# Relays_Multiplexer.net
KiCad netlist of a schematic drawn in EAGLE
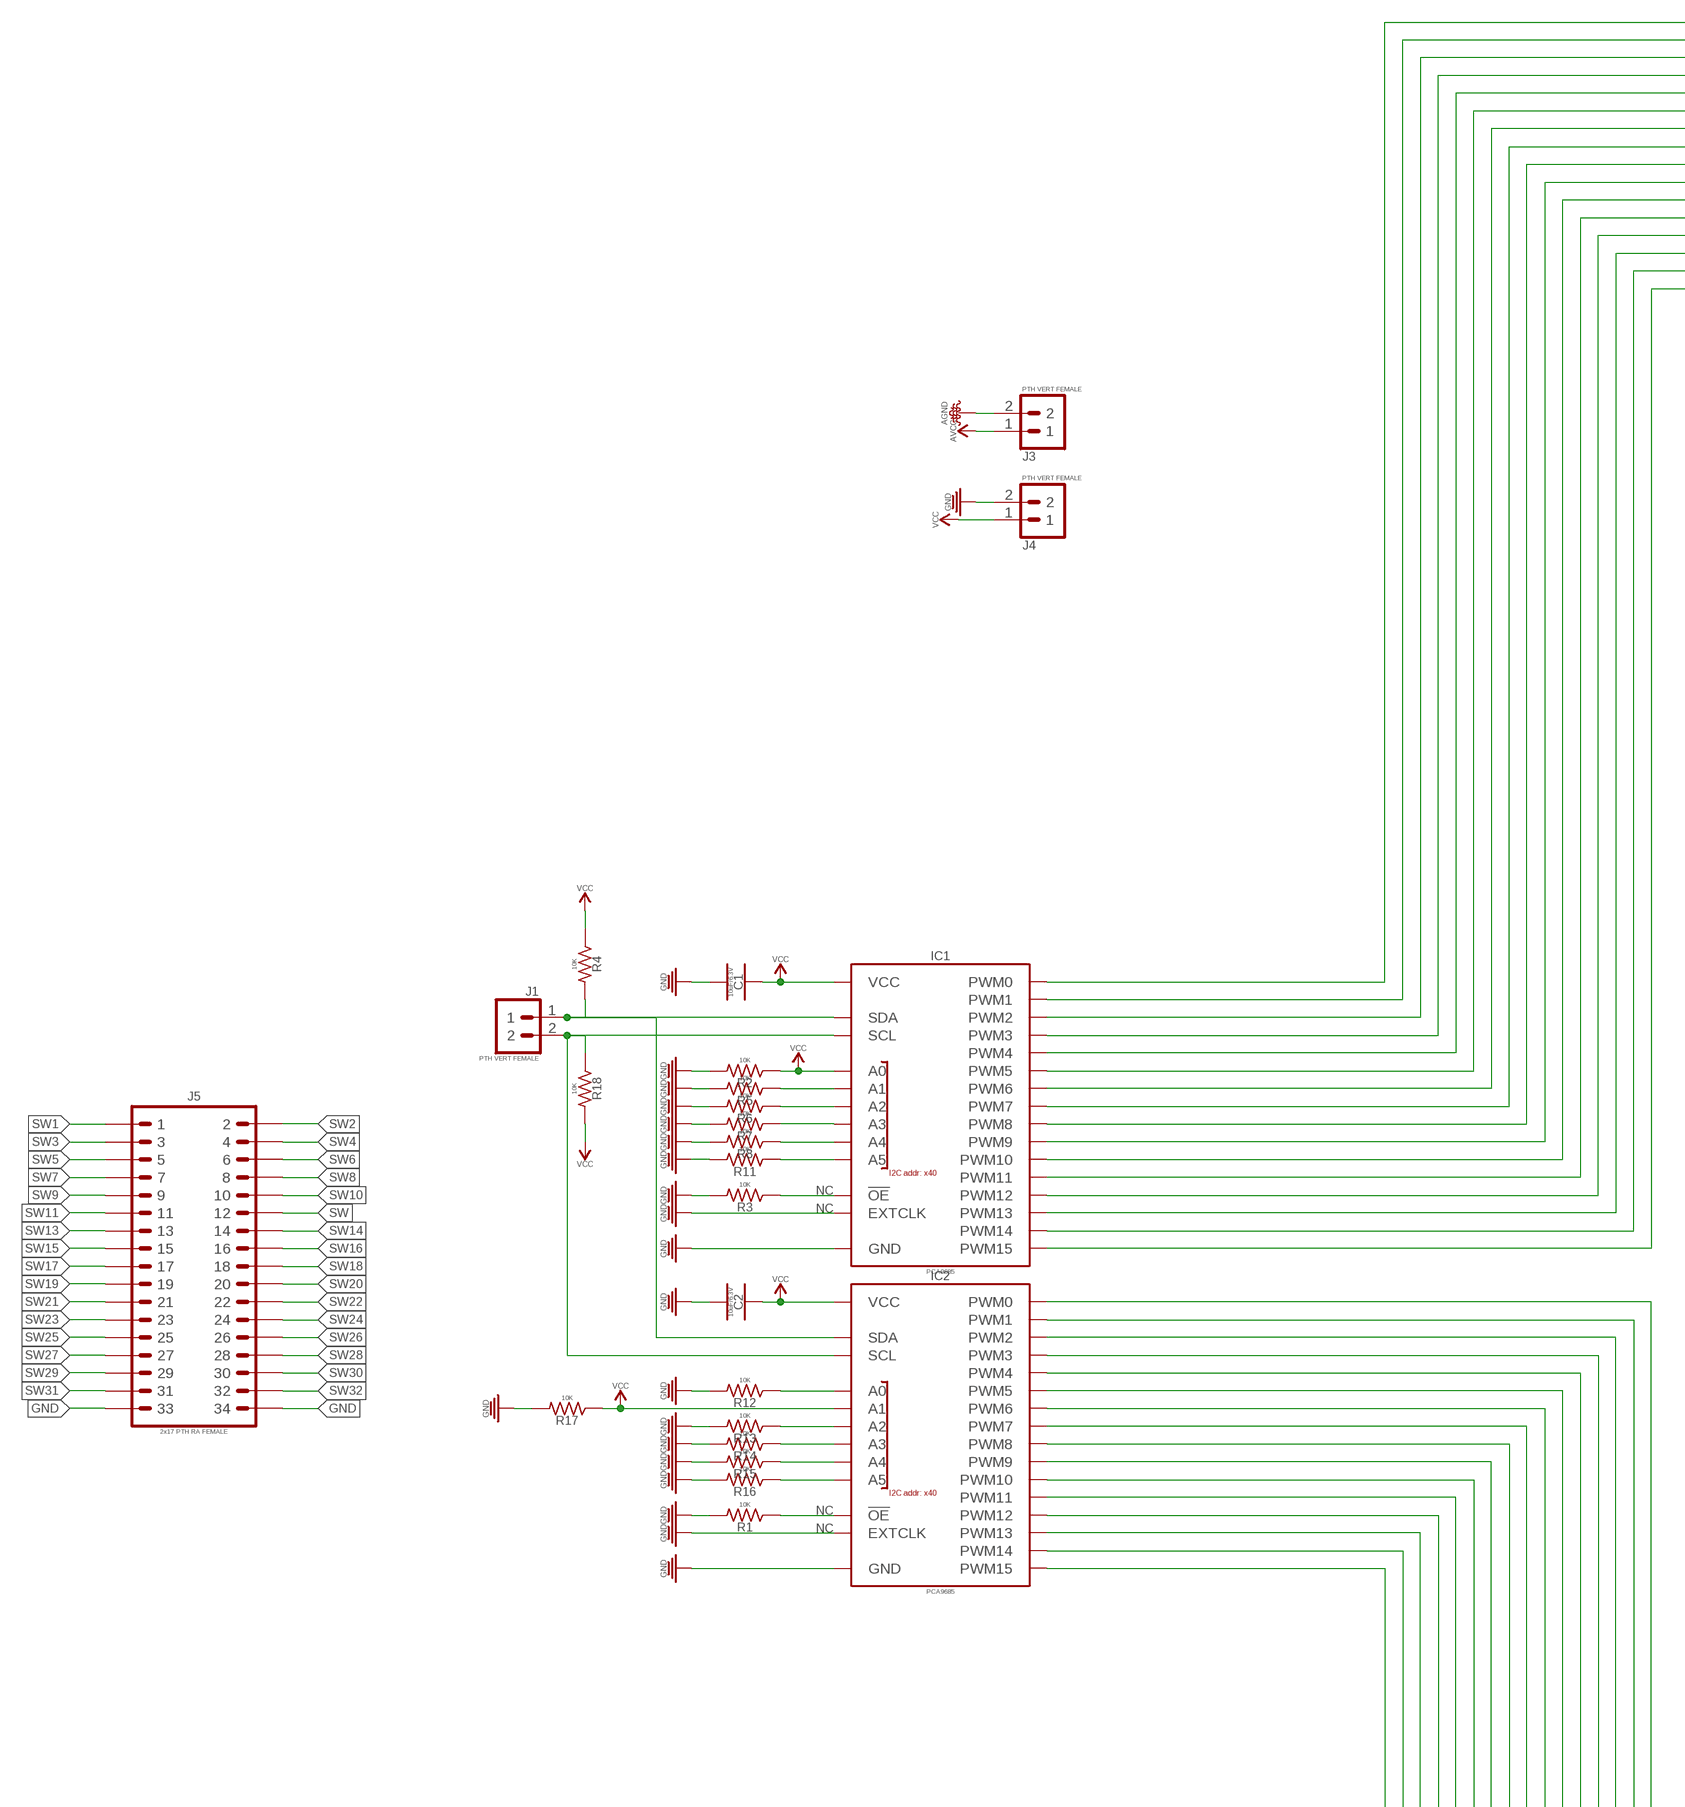
[diagram p0: schematic, sheet 1, part 1 of 3]
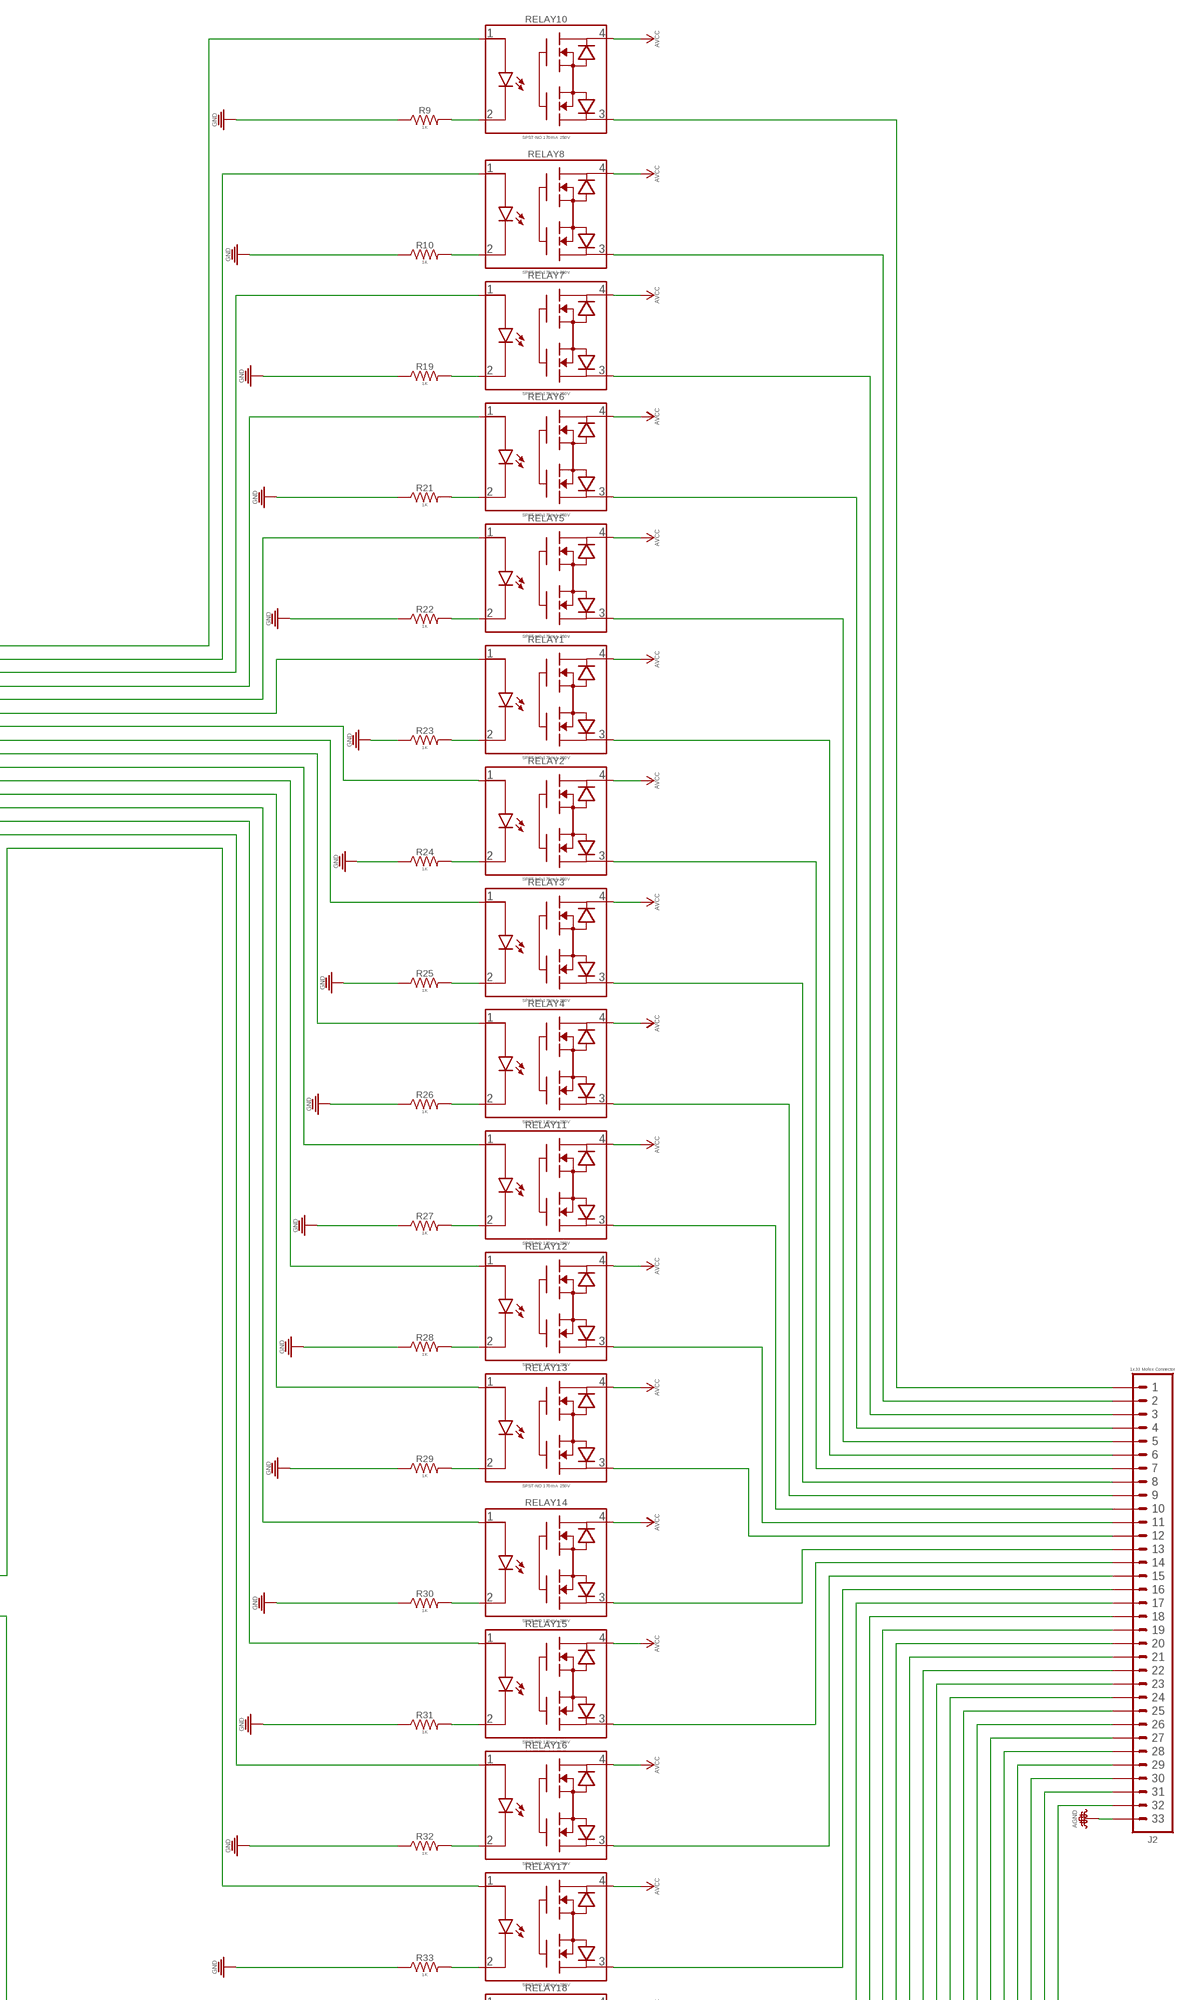
[diagram p1: schematic, sheet 1, part 2 of 3]
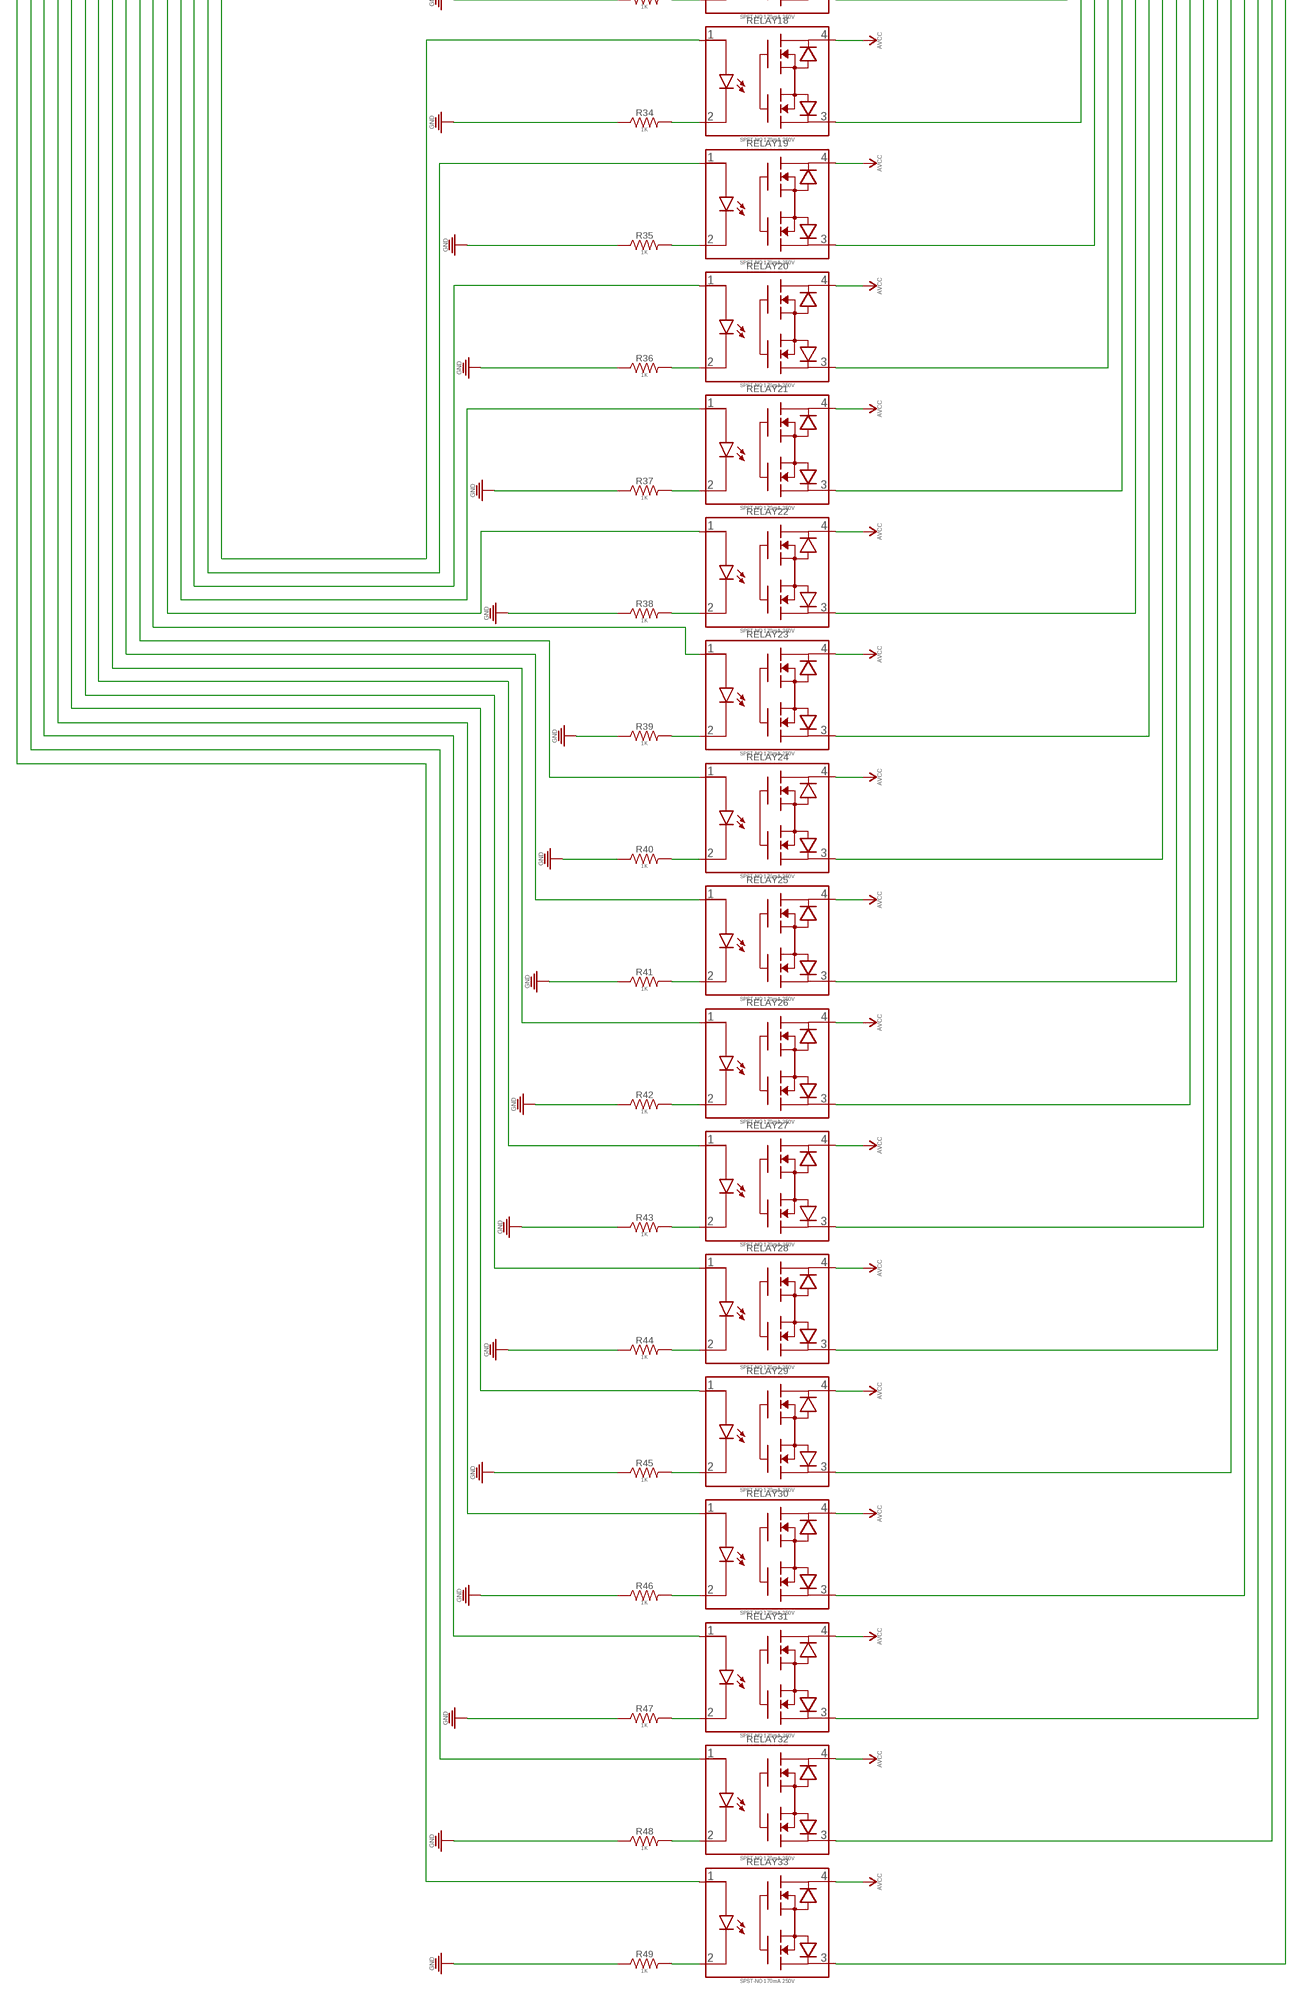
[diagram p2: schematic, sheet 1, part 3 of 3]

(export (version "E")
  (design (tool "Eeschema 10.0.6"))
  (components
    (comp (ref "C1")
      (value "10uF/6.3V")
      (footprint "eagle-import:CAPC1005X55_SMD-0402")
      (fields
        (field (name "MFR") "Murata Electronics North America")
        (field (name "MPN") "GRM155C80J106ME11D")
      )
      (libsource (lib "eagle-import") (part "10UF_CER_SMD-0402_6.3V-20%"))
    )
    (comp (ref "C2")
      (value "10uF/6.3V")
      (footprint "eagle-import:CAPC1005X55_SMD-0402")
      (fields
        (field (name "MFR") "Murata Electronics North America")
        (field (name "MPN") "GRM155C80J106ME11D")
      )
      (libsource (lib "eagle-import") (part "10UF_CER_SMD-0402_6.3V-20%"))
    )
    (comp (ref "IC1")
      (value "PCA9685")
      (footprint "eagle-import:SOP65P650X110-28")
      (fields (field (name "MFR") "NXP USA Inc.") (field (name "MPN") "PCA9685PW,118"))
      (libsource (lib "eagle-import") (part "PCA9685_16-CH_12-BIT_PWM-DRIVER_TSSOP-28_PWM-DRIVER_16CH"))
    )
    (comp (ref "IC2")
      (value "PCA9685")
      (footprint "eagle-import:SOP65P650X110-28")
      (fields (field (name "MFR") "NXP USA Inc.") (field (name "MPN") "PCA9685PW,118"))
      (libsource (lib "eagle-import") (part "PCA9685_16-CH_12-BIT_PWM-DRIVER_TSSOP-28_PWM-DRIVER_16CH"))
    )
    (comp (ref "J1")
      (value "PTH VERT FEMALE")
      (footprint "eagle-import:HDRVR2W64P254_1X2_558X254X850B")
      (fields (field (name "MFR") "Sullins Connector Solutions") (field (name "MPN") "PPTC021LFBN-RC"))
      (libsource (lib "eagle-import") (part "1X02_PTH_VERT_FEMALE_2.54MM"))
    )
    (comp (ref "J2")
      (value "1x33 Molex Connector")
      (footprint "eagle-import:_MOLEX-5025983393_FPC_PITCH-0.3MM")
      (fields (field (name "MFR") "Molex, LLC") (field (name "MPN") "5025983393"))
      (libsource (lib "eagle-import") (part "1X33_MOLEX_FPC_FPC_RIBBON-CABLE"))
    )
    (comp (ref "J3")
      (value "PTH VERT FEMALE")
      (footprint "eagle-import:HDRVR2W64P254_1X2_558X254X850B")
      (fields (field (name "MFR") "Sullins Connector Solutions") (field (name "MPN") "PPTC021LFBN-RC"))
      (libsource (lib "eagle-import") (part "1X02_PTH_VERT_FEMALE_2.54MM"))
    )
    (comp (ref "J4")
      (value "PTH VERT FEMALE")
      (footprint "eagle-import:HDRVR2W64P254_1X2_558X254X850B")
      (fields (field (name "MFR") "Sullins Connector Solutions") (field (name "MPN") "PPTC021LFBN-RC"))
      (libsource (lib "eagle-import") (part "1X02_PTH_VERT_FEMALE_2.54MM"))
    )
    (comp (ref "J5")
      (value "2x17 PTH RA FEMALE")
      (footprint "eagle-import:2X17-RA-FEMALE")
      (fields (field (name "MFR") "Samtec Inc.") (field (name "MPN") "SSQ-117-02-T-D-RA"))
      (libsource (lib "eagle-import") (part "2X17_PTH_RA-FEMALE"))
    )
    (comp (ref "R1")
      (value "10K")
      (footprint "eagle-import:RESC1005X35_SMD-0402")
      (fields (field (name "MFR") "Yageo") (field (name "MPN") "RC0402JR-0710KP"))
      (libsource (lib "eagle-import") (part "10KΩ_SMD-0402_1/16W-5%"))
    )
    (comp (ref "R2")
      (value "10K")
      (footprint "eagle-import:RESC1005X35_SMD-0402")
      (fields (field (name "MFR") "Yageo") (field (name "MPN") "RC0402JR-0710KP"))
      (libsource (lib "eagle-import") (part "10KΩ_SMD-0402_1/16W-5%"))
    )
    (comp (ref "R3")
      (value "10K")
      (footprint "eagle-import:RESC1005X35_SMD-0402")
      (fields (field (name "MFR") "Yageo") (field (name "MPN") "RC0402JR-0710KP"))
      (libsource (lib "eagle-import") (part "10KΩ_SMD-0402_1/16W-5%"))
    )
    (comp (ref "R4")
      (value "10K")
      (footprint "eagle-import:RESC1005X35_SMD-0402")
      (fields (field (name "MFR") "Yageo") (field (name "MPN") "RC0402JR-0710KP"))
      (libsource (lib "eagle-import") (part "10KΩ_SMD-0402_1/16W-5%"))
    )
    (comp (ref "R5")
      (value "10K")
      (footprint "eagle-import:RESC1005X35_SMD-0402")
      (fields (field (name "MFR") "Yageo") (field (name "MPN") "RC0402JR-0710KP"))
      (libsource (lib "eagle-import") (part "10KΩ_SMD-0402_1/16W-5%"))
    )
    (comp (ref "R6")
      (value "10K")
      (footprint "eagle-import:RESC1005X35_SMD-0402")
      (fields (field (name "MFR") "Yageo") (field (name "MPN") "RC0402JR-0710KP"))
      (libsource (lib "eagle-import") (part "10KΩ_SMD-0402_1/16W-5%"))
    )
    (comp (ref "R7")
      (value "10K")
      (footprint "eagle-import:RESC1005X35_SMD-0402")
      (fields (field (name "MFR") "Yageo") (field (name "MPN") "RC0402JR-0710KP"))
      (libsource (lib "eagle-import") (part "10KΩ_SMD-0402_1/16W-5%"))
    )
    (comp (ref "R8")
      (value "10K")
      (footprint "eagle-import:RESC1005X35_SMD-0402")
      (fields (field (name "MFR") "Yageo") (field (name "MPN") "RC0402JR-0710KP"))
      (libsource (lib "eagle-import") (part "10KΩ_SMD-0402_1/16W-5%"))
    )
    (comp (ref "R9")
      (value "1K")
      (footprint "eagle-import:RESC1005X35_SMD-0402")
      (fields (field (name "MFR") "Yageo") (field (name "MPN") "RC0402JR-071KL"))
      (libsource (lib "eagle-import") (part "1KΩ_SMD-0402_1/16W-5%"))
    )
    (comp (ref "R10")
      (value "1K")
      (footprint "eagle-import:RESC1005X35_SMD-0402")
      (fields (field (name "MFR") "Yageo") (field (name "MPN") "RC0402JR-071KL"))
      (libsource (lib "eagle-import") (part "1KΩ_SMD-0402_1/16W-5%"))
    )
    (comp (ref "R11")
      (value "10K")
      (footprint "eagle-import:RESC1005X35_SMD-0402")
      (fields (field (name "MFR") "Yageo") (field (name "MPN") "RC0402JR-0710KP"))
      (libsource (lib "eagle-import") (part "10KΩ_SMD-0402_1/16W-5%"))
    )
    (comp (ref "R12")
      (value "10K")
      (footprint "eagle-import:RESC1005X35_SMD-0402")
      (fields (field (name "MFR") "Yageo") (field (name "MPN") "RC0402JR-0710KP"))
      (libsource (lib "eagle-import") (part "10KΩ_SMD-0402_1/16W-5%"))
    )
    (comp (ref "R13")
      (value "10K")
      (footprint "eagle-import:RESC1005X35_SMD-0402")
      (fields (field (name "MFR") "Yageo") (field (name "MPN") "RC0402JR-0710KP"))
      (libsource (lib "eagle-import") (part "10KΩ_SMD-0402_1/16W-5%"))
    )
    (comp (ref "R14")
      (value "10K")
      (footprint "eagle-import:RESC1005X35_SMD-0402")
      (fields (field (name "MFR") "Yageo") (field (name "MPN") "RC0402JR-0710KP"))
      (libsource (lib "eagle-import") (part "10KΩ_SMD-0402_1/16W-5%"))
    )
    (comp (ref "R15")
      (value "10K")
      (footprint "eagle-import:RESC1005X35_SMD-0402")
      (fields (field (name "MFR") "Yageo") (field (name "MPN") "RC0402JR-0710KP"))
      (libsource (lib "eagle-import") (part "10KΩ_SMD-0402_1/16W-5%"))
    )
    (comp (ref "R16")
      (value "10K")
      (footprint "eagle-import:RESC1005X35_SMD-0402")
      (fields (field (name "MFR") "Yageo") (field (name "MPN") "RC0402JR-0710KP"))
      (libsource (lib "eagle-import") (part "10KΩ_SMD-0402_1/16W-5%"))
    )
    (comp (ref "R17")
      (value "10K")
      (footprint "eagle-import:RESC1005X35_SMD-0402")
      (fields (field (name "MFR") "Yageo") (field (name "MPN") "RC0402JR-0710KP"))
      (libsource (lib "eagle-import") (part "10KΩ_SMD-0402_1/16W-5%"))
    )
    (comp (ref "R18")
      (value "10K")
      (footprint "eagle-import:RESC1005X35_SMD-0402")
      (fields (field (name "MFR") "Yageo") (field (name "MPN") "RC0402JR-0710KP"))
      (libsource (lib "eagle-import") (part "10KΩ_SMD-0402_1/16W-5%"))
    )
    (comp (ref "R19")
      (value "1K")
      (footprint "eagle-import:RESC1005X35_SMD-0402")
      (fields (field (name "MFR") "Yageo") (field (name "MPN") "RC0402JR-071KL"))
      (libsource (lib "eagle-import") (part "1KΩ_SMD-0402_1/16W-5%"))
    )
    (comp (ref "R21")
      (value "1K")
      (footprint "eagle-import:RESC1005X35_SMD-0402")
      (fields (field (name "MFR") "Yageo") (field (name "MPN") "RC0402JR-071KL"))
      (libsource (lib "eagle-import") (part "1KΩ_SMD-0402_1/16W-5%"))
    )
    (comp (ref "R22")
      (value "1K")
      (footprint "eagle-import:RESC1005X35_SMD-0402")
      (fields (field (name "MFR") "Yageo") (field (name "MPN") "RC0402JR-071KL"))
      (libsource (lib "eagle-import") (part "1KΩ_SMD-0402_1/16W-5%"))
    )
    (comp (ref "R23")
      (value "1K")
      (footprint "eagle-import:RESC1005X35_SMD-0402")
      (fields (field (name "MFR") "Yageo") (field (name "MPN") "RC0402JR-071KL"))
      (libsource (lib "eagle-import") (part "1KΩ_SMD-0402_1/16W-5%"))
    )
    (comp (ref "R24")
      (value "1K")
      (footprint "eagle-import:RESC1005X35_SMD-0402")
      (fields (field (name "MFR") "Yageo") (field (name "MPN") "RC0402JR-071KL"))
      (libsource (lib "eagle-import") (part "1KΩ_SMD-0402_1/16W-5%"))
    )
    (comp (ref "R25")
      (value "1K")
      (footprint "eagle-import:RESC1005X35_SMD-0402")
      (fields (field (name "MFR") "Yageo") (field (name "MPN") "RC0402JR-071KL"))
      (libsource (lib "eagle-import") (part "1KΩ_SMD-0402_1/16W-5%"))
    )
    (comp (ref "R26")
      (value "1K")
      (footprint "eagle-import:RESC1005X35_SMD-0402")
      (fields (field (name "MFR") "Yageo") (field (name "MPN") "RC0402JR-071KL"))
      (libsource (lib "eagle-import") (part "1KΩ_SMD-0402_1/16W-5%"))
    )
    (comp (ref "R27")
      (value "1K")
      (footprint "eagle-import:RESC1005X35_SMD-0402")
      (fields (field (name "MFR") "Yageo") (field (name "MPN") "RC0402JR-071KL"))
      (libsource (lib "eagle-import") (part "1KΩ_SMD-0402_1/16W-5%"))
    )
    (comp (ref "R28")
      (value "1K")
      (footprint "eagle-import:RESC1005X35_SMD-0402")
      (fields (field (name "MFR") "Yageo") (field (name "MPN") "RC0402JR-071KL"))
      (libsource (lib "eagle-import") (part "1KΩ_SMD-0402_1/16W-5%"))
    )
    (comp (ref "R29")
      (value "1K")
      (footprint "eagle-import:RESC1005X35_SMD-0402")
      (fields (field (name "MFR") "Yageo") (field (name "MPN") "RC0402JR-071KL"))
      (libsource (lib "eagle-import") (part "1KΩ_SMD-0402_1/16W-5%"))
    )
    (comp (ref "R30")
      (value "1K")
      (footprint "eagle-import:RESC1005X35_SMD-0402")
      (fields (field (name "MFR") "Yageo") (field (name "MPN") "RC0402JR-071KL"))
      (libsource (lib "eagle-import") (part "1KΩ_SMD-0402_1/16W-5%"))
    )
    (comp (ref "R31")
      (value "1K")
      (footprint "eagle-import:RESC1005X35_SMD-0402")
      (fields (field (name "MFR") "Yageo") (field (name "MPN") "RC0402JR-071KL"))
      (libsource (lib "eagle-import") (part "1KΩ_SMD-0402_1/16W-5%"))
    )
    (comp (ref "R32")
      (value "1K")
      (footprint "eagle-import:RESC1005X35_SMD-0402")
      (fields (field (name "MFR") "Yageo") (field (name "MPN") "RC0402JR-071KL"))
      (libsource (lib "eagle-import") (part "1KΩ_SMD-0402_1/16W-5%"))
    )
    (comp (ref "R33")
      (value "1K")
      (footprint "eagle-import:RESC1005X35_SMD-0402")
      (fields (field (name "MFR") "Yageo") (field (name "MPN") "RC0402JR-071KL"))
      (libsource (lib "eagle-import") (part "1KΩ_SMD-0402_1/16W-5%"))
    )
    (comp (ref "R34")
      (value "1K")
      (footprint "eagle-import:RESC1005X35_SMD-0402")
      (fields (field (name "MFR") "Yageo") (field (name "MPN") "RC0402JR-071KL"))
      (libsource (lib "eagle-import") (part "1KΩ_SMD-0402_1/16W-5%"))
    )
    (comp (ref "R35")
      (value "1K")
      (footprint "eagle-import:RESC1005X35_SMD-0402")
      (fields (field (name "MFR") "Yageo") (field (name "MPN") "RC0402JR-071KL"))
      (libsource (lib "eagle-import") (part "1KΩ_SMD-0402_1/16W-5%"))
    )
    (comp (ref "R36")
      (value "1K")
      (footprint "eagle-import:RESC1005X35_SMD-0402")
      (fields (field (name "MFR") "Yageo") (field (name "MPN") "RC0402JR-071KL"))
      (libsource (lib "eagle-import") (part "1KΩ_SMD-0402_1/16W-5%"))
    )
    (comp (ref "R37")
      (value "1K")
      (footprint "eagle-import:RESC1005X35_SMD-0402")
      (fields (field (name "MFR") "Yageo") (field (name "MPN") "RC0402JR-071KL"))
      (libsource (lib "eagle-import") (part "1KΩ_SMD-0402_1/16W-5%"))
    )
    (comp (ref "R38")
      (value "1K")
      (footprint "eagle-import:RESC1005X35_SMD-0402")
      (fields (field (name "MFR") "Yageo") (field (name "MPN") "RC0402JR-071KL"))
      (libsource (lib "eagle-import") (part "1KΩ_SMD-0402_1/16W-5%"))
    )
    (comp (ref "R39")
      (value "1K")
      (footprint "eagle-import:RESC1005X35_SMD-0402")
      (fields (field (name "MFR") "Yageo") (field (name "MPN") "RC0402JR-071KL"))
      (libsource (lib "eagle-import") (part "1KΩ_SMD-0402_1/16W-5%"))
    )
    (comp (ref "R40")
      (value "1K")
      (footprint "eagle-import:RESC1005X35_SMD-0402")
      (fields (field (name "MFR") "Yageo") (field (name "MPN") "RC0402JR-071KL"))
      (libsource (lib "eagle-import") (part "1KΩ_SMD-0402_1/16W-5%"))
    )
    (comp (ref "R41")
      (value "1K")
      (footprint "eagle-import:RESC1005X35_SMD-0402")
      (fields (field (name "MFR") "Yageo") (field (name "MPN") "RC0402JR-071KL"))
      (libsource (lib "eagle-import") (part "1KΩ_SMD-0402_1/16W-5%"))
    )
    (comp (ref "R42")
      (value "1K")
      (footprint "eagle-import:RESC1005X35_SMD-0402")
      (fields (field (name "MFR") "Yageo") (field (name "MPN") "RC0402JR-071KL"))
      (libsource (lib "eagle-import") (part "1KΩ_SMD-0402_1/16W-5%"))
    )
    (comp (ref "R43")
      (value "1K")
      (footprint "eagle-import:RESC1005X35_SMD-0402")
      (fields (field (name "MFR") "Yageo") (field (name "MPN") "RC0402JR-071KL"))
      (libsource (lib "eagle-import") (part "1KΩ_SMD-0402_1/16W-5%"))
    )
    (comp (ref "R44")
      (value "1K")
      (footprint "eagle-import:RESC1005X35_SMD-0402")
      (fields (field (name "MFR") "Yageo") (field (name "MPN") "RC0402JR-071KL"))
      (libsource (lib "eagle-import") (part "1KΩ_SMD-0402_1/16W-5%"))
    )
    (comp (ref "R45")
      (value "1K")
      (footprint "eagle-import:RESC1005X35_SMD-0402")
      (fields (field (name "MFR") "Yageo") (field (name "MPN") "RC0402JR-071KL"))
      (libsource (lib "eagle-import") (part "1KΩ_SMD-0402_1/16W-5%"))
    )
    (comp (ref "R46")
      (value "1K")
      (footprint "eagle-import:RESC1005X35_SMD-0402")
      (fields (field (name "MFR") "Yageo") (field (name "MPN") "RC0402JR-071KL"))
      (libsource (lib "eagle-import") (part "1KΩ_SMD-0402_1/16W-5%"))
    )
    (comp (ref "R47")
      (value "1K")
      (footprint "eagle-import:RESC1005X35_SMD-0402")
      (fields (field (name "MFR") "Yageo") (field (name "MPN") "RC0402JR-071KL"))
      (libsource (lib "eagle-import") (part "1KΩ_SMD-0402_1/16W-5%"))
    )
    (comp (ref "R48")
      (value "1K")
      (footprint "eagle-import:RESC1005X35_SMD-0402")
      (fields (field (name "MFR") "Yageo") (field (name "MPN") "RC0402JR-071KL"))
      (libsource (lib "eagle-import") (part "1KΩ_SMD-0402_1/16W-5%"))
    )
    (comp (ref "R49")
      (value "1K")
      (footprint "eagle-import:RESC1005X35_SMD-0402")
      (fields (field (name "MFR") "Yageo") (field (name "MPN") "RC0402JR-071KL"))
      (libsource (lib "eagle-import") (part "1KΩ_SMD-0402_1/16W-5%"))
    )
    (comp (ref "RELAY1")
      (value "SPST-NO 170mA 250V")
      (footprint "eagle-import:SOP254P609X203-4")
      (fields (field (name "MFR") "IXYS Integrated Circuits Division") (field (name "MPN") "CPC1010N"))
      (libsource (lib "eagle-import") (part "RELAY_SOLID-STATE_SSR_170MA_250V_SPST-NO"))
    )
    (comp (ref "RELAY2")
      (value "SPST-NO 170mA 250V")
      (footprint "eagle-import:SOP254P609X203-4")
      (fields (field (name "MFR") "IXYS Integrated Circuits Division") (field (name "MPN") "CPC1010N"))
      (libsource (lib "eagle-import") (part "RELAY_SOLID-STATE_SSR_170MA_250V_SPST-NO"))
    )
    (comp (ref "RELAY3")
      (value "SPST-NO 170mA 250V")
      (footprint "eagle-import:SOP254P609X203-4")
      (fields (field (name "MFR") "IXYS Integrated Circuits Division") (field (name "MPN") "CPC1010N"))
      (libsource (lib "eagle-import") (part "RELAY_SOLID-STATE_SSR_170MA_250V_SPST-NO"))
    )
    (comp (ref "RELAY4")
      (value "SPST-NO 170mA 250V")
      (footprint "eagle-import:SOP254P609X203-4")
      (fields (field (name "MFR") "IXYS Integrated Circuits Division") (field (name "MPN") "CPC1010N"))
      (libsource (lib "eagle-import") (part "RELAY_SOLID-STATE_SSR_170MA_250V_SPST-NO"))
    )
    (comp (ref "RELAY5")
      (value "SPST-NO 170mA 250V")
      (footprint "eagle-import:SOP254P609X203-4")
      (fields (field (name "MFR") "IXYS Integrated Circuits Division") (field (name "MPN") "CPC1010N"))
      (libsource (lib "eagle-import") (part "RELAY_SOLID-STATE_SSR_170MA_250V_SPST-NO"))
    )
    (comp (ref "RELAY6")
      (value "SPST-NO 170mA 250V")
      (footprint "eagle-import:SOP254P609X203-4")
      (fields (field (name "MFR") "IXYS Integrated Circuits Division") (field (name "MPN") "CPC1010N"))
      (libsource (lib "eagle-import") (part "RELAY_SOLID-STATE_SSR_170MA_250V_SPST-NO"))
    )
    (comp (ref "RELAY7")
      (value "SPST-NO 170mA 250V")
      (footprint "eagle-import:SOP254P609X203-4")
      (fields (field (name "MFR") "IXYS Integrated Circuits Division") (field (name "MPN") "CPC1010N"))
      (libsource (lib "eagle-import") (part "RELAY_SOLID-STATE_SSR_170MA_250V_SPST-NO"))
    )
    (comp (ref "RELAY8")
      (value "SPST-NO 170mA 250V")
      (footprint "eagle-import:SOP254P609X203-4")
      (fields (field (name "MFR") "IXYS Integrated Circuits Division") (field (name "MPN") "CPC1010N"))
      (libsource (lib "eagle-import") (part "RELAY_SOLID-STATE_SSR_170MA_250V_SPST-NO"))
    )
    (comp (ref "RELAY10")
      (value "SPST-NO 170mA 250V")
      (footprint "eagle-import:SOP254P609X203-4")
      (fields (field (name "MFR") "IXYS Integrated Circuits Division") (field (name "MPN") "CPC1010N"))
      (libsource (lib "eagle-import") (part "RELAY_SOLID-STATE_SSR_170MA_250V_SPST-NO"))
    )
    (comp (ref "RELAY11")
      (value "SPST-NO 170mA 250V")
      (footprint "eagle-import:SOP254P609X203-4")
      (fields (field (name "MFR") "IXYS Integrated Circuits Division") (field (name "MPN") "CPC1010N"))
      (libsource (lib "eagle-import") (part "RELAY_SOLID-STATE_SSR_170MA_250V_SPST-NO"))
    )
    (comp (ref "RELAY12")
      (value "SPST-NO 170mA 250V")
      (footprint "eagle-import:SOP254P609X203-4")
      (fields (field (name "MFR") "IXYS Integrated Circuits Division") (field (name "MPN") "CPC1010N"))
      (libsource (lib "eagle-import") (part "RELAY_SOLID-STATE_SSR_170MA_250V_SPST-NO"))
    )
    (comp (ref "RELAY13")
      (value "SPST-NO 170mA 250V")
      (footprint "eagle-import:SOP254P609X203-4")
      (fields (field (name "MFR") "IXYS Integrated Circuits Division") (field (name "MPN") "CPC1010N"))
      (libsource (lib "eagle-import") (part "RELAY_SOLID-STATE_SSR_170MA_250V_SPST-NO"))
    )
    (comp (ref "RELAY14")
      (value "SPST-NO 170mA 250V")
      (footprint "eagle-import:SOP254P609X203-4")
      (fields (field (name "MFR") "IXYS Integrated Circuits Division") (field (name "MPN") "CPC1010N"))
      (libsource (lib "eagle-import") (part "RELAY_SOLID-STATE_SSR_170MA_250V_SPST-NO"))
    )
    (comp (ref "RELAY15")
      (value "SPST-NO 170mA 250V")
      (footprint "eagle-import:SOP254P609X203-4")
      (fields (field (name "MFR") "IXYS Integrated Circuits Division") (field (name "MPN") "CPC1010N"))
      (libsource (lib "eagle-import") (part "RELAY_SOLID-STATE_SSR_170MA_250V_SPST-NO"))
    )
    (comp (ref "RELAY16")
      (value "SPST-NO 170mA 250V")
      (footprint "eagle-import:SOP254P609X203-4")
      (fields (field (name "MFR") "IXYS Integrated Circuits Division") (field (name "MPN") "CPC1010N"))
      (libsource (lib "eagle-import") (part "RELAY_SOLID-STATE_SSR_170MA_250V_SPST-NO"))
    )
    (comp (ref "RELAY17")
      (value "SPST-NO 170mA 250V")
      (footprint "eagle-import:SOP254P609X203-4")
      (fields (field (name "MFR") "IXYS Integrated Circuits Division") (field (name "MPN") "CPC1010N"))
      (libsource (lib "eagle-import") (part "RELAY_SOLID-STATE_SSR_170MA_250V_SPST-NO"))
    )
    (comp (ref "RELAY18")
      (value "SPST-NO 170mA 250V")
      (footprint "eagle-import:SOP254P609X203-4")
      (fields (field (name "MFR") "IXYS Integrated Circuits Division") (field (name "MPN") "CPC1010N"))
      (libsource (lib "eagle-import") (part "RELAY_SOLID-STATE_SSR_170MA_250V_SPST-NO"))
    )
    (comp (ref "RELAY19")
      (value "SPST-NO 170mA 250V")
      (footprint "eagle-import:SOP254P609X203-4")
      (fields (field (name "MFR") "IXYS Integrated Circuits Division") (field (name "MPN") "CPC1010N"))
      (libsource (lib "eagle-import") (part "RELAY_SOLID-STATE_SSR_170MA_250V_SPST-NO"))
    )
    (comp (ref "RELAY20")
      (value "SPST-NO 170mA 250V")
      (footprint "eagle-import:SOP254P609X203-4")
      (fields (field (name "MFR") "IXYS Integrated Circuits Division") (field (name "MPN") "CPC1010N"))
      (libsource (lib "eagle-import") (part "RELAY_SOLID-STATE_SSR_170MA_250V_SPST-NO"))
    )
    (comp (ref "RELAY21")
      (value "SPST-NO 170mA 250V")
      (footprint "eagle-import:SOP254P609X203-4")
      (fields (field (name "MFR") "IXYS Integrated Circuits Division") (field (name "MPN") "CPC1010N"))
      (libsource (lib "eagle-import") (part "RELAY_SOLID-STATE_SSR_170MA_250V_SPST-NO"))
    )
    (comp (ref "RELAY22")
      (value "SPST-NO 170mA 250V")
      (footprint "eagle-import:SOP254P609X203-4")
      (fields (field (name "MFR") "IXYS Integrated Circuits Division") (field (name "MPN") "CPC1010N"))
      (libsource (lib "eagle-import") (part "RELAY_SOLID-STATE_SSR_170MA_250V_SPST-NO"))
    )
    (comp (ref "RELAY23")
      (value "SPST-NO 170mA 250V")
      (footprint "eagle-import:SOP254P609X203-4")
      (fields (field (name "MFR") "IXYS Integrated Circuits Division") (field (name "MPN") "CPC1010N"))
      (libsource (lib "eagle-import") (part "RELAY_SOLID-STATE_SSR_170MA_250V_SPST-NO"))
    )
    (comp (ref "RELAY24")
      (value "SPST-NO 170mA 250V")
      (footprint "eagle-import:SOP254P609X203-4")
      (fields (field (name "MFR") "IXYS Integrated Circuits Division") (field (name "MPN") "CPC1010N"))
      (libsource (lib "eagle-import") (part "RELAY_SOLID-STATE_SSR_170MA_250V_SPST-NO"))
    )
    (comp (ref "RELAY25")
      (value "SPST-NO 170mA 250V")
      (footprint "eagle-import:SOP254P609X203-4")
      (fields (field (name "MFR") "IXYS Integrated Circuits Division") (field (name "MPN") "CPC1010N"))
      (libsource (lib "eagle-import") (part "RELAY_SOLID-STATE_SSR_170MA_250V_SPST-NO"))
    )
    (comp (ref "RELAY26")
      (value "SPST-NO 170mA 250V")
      (footprint "eagle-import:SOP254P609X203-4")
      (fields (field (name "MFR") "IXYS Integrated Circuits Division") (field (name "MPN") "CPC1010N"))
      (libsource (lib "eagle-import") (part "RELAY_SOLID-STATE_SSR_170MA_250V_SPST-NO"))
    )
    (comp (ref "RELAY27")
      (value "SPST-NO 170mA 250V")
      (footprint "eagle-import:SOP254P609X203-4")
      (fields (field (name "MFR") "IXYS Integrated Circuits Division") (field (name "MPN") "CPC1010N"))
      (libsource (lib "eagle-import") (part "RELAY_SOLID-STATE_SSR_170MA_250V_SPST-NO"))
    )
    (comp (ref "RELAY28")
      (value "SPST-NO 170mA 250V")
      (footprint "eagle-import:SOP254P609X203-4")
      (fields (field (name "MFR") "IXYS Integrated Circuits Division") (field (name "MPN") "CPC1010N"))
      (libsource (lib "eagle-import") (part "RELAY_SOLID-STATE_SSR_170MA_250V_SPST-NO"))
    )
    (comp (ref "RELAY29")
      (value "SPST-NO 170mA 250V")
      (footprint "eagle-import:SOP254P609X203-4")
      (fields (field (name "MFR") "IXYS Integrated Circuits Division") (field (name "MPN") "CPC1010N"))
      (libsource (lib "eagle-import") (part "RELAY_SOLID-STATE_SSR_170MA_250V_SPST-NO"))
    )
    (comp (ref "RELAY30")
      (value "SPST-NO 170mA 250V")
      (footprint "eagle-import:SOP254P609X203-4")
      (fields (field (name "MFR") "IXYS Integrated Circuits Division") (field (name "MPN") "CPC1010N"))
      (libsource (lib "eagle-import") (part "RELAY_SOLID-STATE_SSR_170MA_250V_SPST-NO"))
    )
    (comp (ref "RELAY31")
      (value "SPST-NO 170mA 250V")
      (footprint "eagle-import:SOP254P609X203-4")
      (fields (field (name "MFR") "IXYS Integrated Circuits Division") (field (name "MPN") "CPC1010N"))
      (libsource (lib "eagle-import") (part "RELAY_SOLID-STATE_SSR_170MA_250V_SPST-NO"))
    )
    (comp (ref "RELAY32")
      (value "SPST-NO 170mA 250V")
      (footprint "eagle-import:SOP254P609X203-4")
      (fields (field (name "MFR") "IXYS Integrated Circuits Division") (field (name "MPN") "CPC1010N"))
      (libsource (lib "eagle-import") (part "RELAY_SOLID-STATE_SSR_170MA_250V_SPST-NO"))
    )
    (comp (ref "RELAY33")
      (value "SPST-NO 170mA 250V")
      (footprint "eagle-import:SOP254P609X203-4")
      (fields (field (name "MFR") "IXYS Integrated Circuits Division") (field (name "MPN") "CPC1010N"))
      (libsource (lib "eagle-import") (part "RELAY_SOLID-STATE_SSR_170MA_250V_SPST-NO"))
    )
  )
  (nets
    (net (code "1") (name "AGND") (class "Default")
      (node (ref "J2") (pin "P$33") (pinfunction "33_P$33") (pintype "passive"))
      (node (ref "J3") (pin "2") (pinfunction "2_2") (pintype "passive"))
    )
    (net (code "2") (name "AVCC") (class "Default")
      (node (ref "J3") (pin "1") (pinfunction "1_1") (pintype "passive"))
      (node (ref "RELAY1") (pin "4") (pinfunction "4_4") (pintype "bidirectional"))
      (node (ref "RELAY10") (pin "4") (pinfunction "4_4") (pintype "bidirectional"))
      (node (ref "RELAY11") (pin "4") (pinfunction "4_4") (pintype "bidirectional"))
      (node (ref "RELAY12") (pin "4") (pinfunction "4_4") (pintype "bidirectional"))
      (node (ref "RELAY13") (pin "4") (pinfunction "4_4") (pintype "bidirectional"))
      (node (ref "RELAY14") (pin "4") (pinfunction "4_4") (pintype "bidirectional"))
      (node (ref "RELAY15") (pin "4") (pinfunction "4_4") (pintype "bidirectional"))
      (node (ref "RELAY16") (pin "4") (pinfunction "4_4") (pintype "bidirectional"))
      (node (ref "RELAY17") (pin "4") (pinfunction "4_4") (pintype "bidirectional"))
      (node (ref "RELAY18") (pin "4") (pinfunction "4_4") (pintype "bidirectional"))
      (node (ref "RELAY19") (pin "4") (pinfunction "4_4") (pintype "bidirectional"))
      (node (ref "RELAY2") (pin "4") (pinfunction "4_4") (pintype "bidirectional"))
      (node (ref "RELAY20") (pin "4") (pinfunction "4_4") (pintype "bidirectional"))
      (node (ref "RELAY21") (pin "4") (pinfunction "4_4") (pintype "bidirectional"))
      (node (ref "RELAY22") (pin "4") (pinfunction "4_4") (pintype "bidirectional"))
      (node (ref "RELAY23") (pin "4") (pinfunction "4_4") (pintype "bidirectional"))
      (node (ref "RELAY24") (pin "4") (pinfunction "4_4") (pintype "bidirectional"))
      (node (ref "RELAY25") (pin "4") (pinfunction "4_4") (pintype "bidirectional"))
      (node (ref "RELAY26") (pin "4") (pinfunction "4_4") (pintype "bidirectional"))
      (node (ref "RELAY27") (pin "4") (pinfunction "4_4") (pintype "bidirectional"))
      (node (ref "RELAY28") (pin "4") (pinfunction "4_4") (pintype "bidirectional"))
      (node (ref "RELAY29") (pin "4") (pinfunction "4_4") (pintype "bidirectional"))
      (node (ref "RELAY3") (pin "4") (pinfunction "4_4") (pintype "bidirectional"))
      (node (ref "RELAY30") (pin "4") (pinfunction "4_4") (pintype "bidirectional"))
      (node (ref "RELAY31") (pin "4") (pinfunction "4_4") (pintype "bidirectional"))
      (node (ref "RELAY32") (pin "4") (pinfunction "4_4") (pintype "bidirectional"))
      (node (ref "RELAY33") (pin "4") (pinfunction "4_4") (pintype "bidirectional"))
      (node (ref "RELAY4") (pin "4") (pinfunction "4_4") (pintype "bidirectional"))
      (node (ref "RELAY5") (pin "4") (pinfunction "4_4") (pintype "bidirectional"))
      (node (ref "RELAY6") (pin "4") (pinfunction "4_4") (pintype "bidirectional"))
      (node (ref "RELAY7") (pin "4") (pinfunction "4_4") (pintype "bidirectional"))
      (node (ref "RELAY8") (pin "4") (pinfunction "4_4") (pintype "bidirectional"))
    )
    (net (code "3") (name "GND") (class "Default")
      (node (ref "C1") (pin "2") (pinfunction "2_2") (pintype "passive"))
      (node (ref "C2") (pin "2") (pinfunction "2_2") (pintype "passive"))
      (node (ref "IC1") (pin "14") (pinfunction "GND_14") (pintype "power_in"))
      (node (ref "IC1") (pin "25") (pinfunction "EXTCLK_25") (pintype "power_in"))
      (node (ref "IC2") (pin "14") (pinfunction "GND_14") (pintype "power_in"))
      (node (ref "IC2") (pin "25") (pinfunction "EXTCLK_25") (pintype "power_in"))
      (node (ref "J4") (pin "2") (pinfunction "2_2") (pintype "passive"))
      (node (ref "J5") (pin "33") (pinfunction "33_33") (pintype "passive"))
      (node (ref "J5") (pin "34") (pinfunction "34_34") (pintype "passive"))
      (node (ref "R1") (pin "2") (pinfunction "2_2") (pintype "passive"))
      (node (ref "R10") (pin "1") (pinfunction "1_1") (pintype "passive"))
      (node (ref "R11") (pin "2") (pinfunction "2_2") (pintype "passive"))
      (node (ref "R12") (pin "2") (pinfunction "2_2") (pintype "passive"))
      (node (ref "R13") (pin "2") (pinfunction "2_2") (pintype "passive"))
      (node (ref "R14") (pin "2") (pinfunction "2_2") (pintype "passive"))
      (node (ref "R15") (pin "2") (pinfunction "2_2") (pintype "passive"))
      (node (ref "R16") (pin "2") (pinfunction "2_2") (pintype "passive"))
      (node (ref "R17") (pin "2") (pinfunction "2_2") (pintype "passive"))
      (node (ref "R19") (pin "1") (pinfunction "1_1") (pintype "passive"))
      (node (ref "R2") (pin "2") (pinfunction "2_2") (pintype "passive"))
      (node (ref "R21") (pin "1") (pinfunction "1_1") (pintype "passive"))
      (node (ref "R22") (pin "1") (pinfunction "1_1") (pintype "passive"))
      (node (ref "R23") (pin "1") (pinfunction "1_1") (pintype "passive"))
      (node (ref "R24") (pin "1") (pinfunction "1_1") (pintype "passive"))
      (node (ref "R25") (pin "1") (pinfunction "1_1") (pintype "passive"))
      (node (ref "R26") (pin "1") (pinfunction "1_1") (pintype "passive"))
      (node (ref "R27") (pin "1") (pinfunction "1_1") (pintype "passive"))
      (node (ref "R28") (pin "1") (pinfunction "1_1") (pintype "passive"))
      (node (ref "R29") (pin "1") (pinfunction "1_1") (pintype "passive"))
      (node (ref "R3") (pin "2") (pinfunction "2_2") (pintype "passive"))
      (node (ref "R30") (pin "1") (pinfunction "1_1") (pintype "passive"))
      (node (ref "R31") (pin "1") (pinfunction "1_1") (pintype "passive"))
      (node (ref "R32") (pin "1") (pinfunction "1_1") (pintype "passive"))
      (node (ref "R33") (pin "1") (pinfunction "1_1") (pintype "passive"))
      (node (ref "R34") (pin "1") (pinfunction "1_1") (pintype "passive"))
      (node (ref "R35") (pin "1") (pinfunction "1_1") (pintype "passive"))
      (node (ref "R36") (pin "1") (pinfunction "1_1") (pintype "passive"))
      (node (ref "R37") (pin "1") (pinfunction "1_1") (pintype "passive"))
      (node (ref "R38") (pin "1") (pinfunction "1_1") (pintype "passive"))
      (node (ref "R39") (pin "1") (pinfunction "1_1") (pintype "passive"))
      (node (ref "R40") (pin "1") (pinfunction "1_1") (pintype "passive"))
      (node (ref "R41") (pin "1") (pinfunction "1_1") (pintype "passive"))
      (node (ref "R42") (pin "1") (pinfunction "1_1") (pintype "passive"))
      (node (ref "R43") (pin "1") (pinfunction "1_1") (pintype "passive"))
      (node (ref "R44") (pin "1") (pinfunction "1_1") (pintype "passive"))
      (node (ref "R45") (pin "1") (pinfunction "1_1") (pintype "passive"))
      (node (ref "R46") (pin "1") (pinfunction "1_1") (pintype "passive"))
      (node (ref "R47") (pin "1") (pinfunction "1_1") (pintype "passive"))
      (node (ref "R48") (pin "1") (pinfunction "1_1") (pintype "passive"))
      (node (ref "R49") (pin "1") (pinfunction "1_1") (pintype "passive"))
      (node (ref "R5") (pin "2") (pinfunction "2_2") (pintype "passive"))
      (node (ref "R6") (pin "2") (pinfunction "2_2") (pintype "passive"))
      (node (ref "R7") (pin "2") (pinfunction "2_2") (pintype "passive"))
      (node (ref "R8") (pin "2") (pinfunction "2_2") (pintype "passive"))
      (node (ref "R9") (pin "1") (pinfunction "1_1") (pintype "passive"))
    )
    (net (code "4") (name "Net-(IC1-A1)") (class "Default")
      (node (ref "IC1") (pin "2") (pinfunction "A1_2") (pintype "power_in"))
      (node (ref "R5") (pin "1") (pinfunction "1_1") (pintype "passive"))
    )
    (net (code "5") (name "Net-(IC1-A2)") (class "Default")
      (node (ref "IC1") (pin "3") (pinfunction "A2_3") (pintype "power_in"))
      (node (ref "R6") (pin "1") (pinfunction "1_1") (pintype "passive"))
    )
    (net (code "6") (name "Net-(IC1-A3)") (class "Default")
      (node (ref "IC1") (pin "4") (pinfunction "A3_4") (pintype "power_in"))
      (node (ref "R7") (pin "1") (pinfunction "1_1") (pintype "passive"))
    )
    (net (code "7") (name "Net-(IC1-A4)") (class "Default")
      (node (ref "IC1") (pin "5") (pinfunction "A4_5") (pintype "power_in"))
      (node (ref "R8") (pin "1") (pinfunction "1_1") (pintype "passive"))
    )
    (net (code "8") (name "Net-(IC1-A5)") (class "Default")
      (node (ref "IC1") (pin "24") (pinfunction "A5_24") (pintype "power_in"))
      (node (ref "R11") (pin "1") (pinfunction "1_1") (pintype "passive"))
    )
    (net (code "9") (name "Net-(IC1-SCL)") (class "Default")
      (node (ref "IC1") (pin "26") (pinfunction "SCL_26") (pintype "bidirectional"))
      (node (ref "IC2") (pin "26") (pinfunction "SCL_26") (pintype "bidirectional"))
      (node (ref "J1") (pin "2") (pinfunction "2_2") (pintype "passive"))
      (node (ref "R18") (pin "1") (pinfunction "1_1") (pintype "passive"))
    )
    (net (code "10") (name "Net-(IC1-SDA)") (class "Default")
      (node (ref "IC1") (pin "27") (pinfunction "SDA_27") (pintype "bidirectional"))
      (node (ref "IC2") (pin "27") (pinfunction "SDA_27") (pintype "bidirectional"))
      (node (ref "J1") (pin "1") (pinfunction "1_1") (pintype "passive"))
      (node (ref "R4") (pin "2") (pinfunction "2_2") (pintype "passive"))
    )
    (net (code "11") (name "Net-(IC1-~{OE})") (class "Default")
      (node (ref "IC1") (pin "23") (pinfunction "~{OE}_23") (pintype "power_in"))
      (node (ref "R3") (pin "1") (pinfunction "1_1") (pintype "passive"))
    )
    (net (code "12") (name "Net-(IC2-A0)") (class "Default")
      (node (ref "IC2") (pin "1") (pinfunction "A0_1") (pintype "power_in"))
      (node (ref "R12") (pin "1") (pinfunction "1_1") (pintype "passive"))
    )
    (net (code "13") (name "Net-(IC2-A2)") (class "Default")
      (node (ref "IC2") (pin "3") (pinfunction "A2_3") (pintype "power_in"))
      (node (ref "R13") (pin "1") (pinfunction "1_1") (pintype "passive"))
    )
    (net (code "14") (name "Net-(IC2-A3)") (class "Default")
      (node (ref "IC2") (pin "4") (pinfunction "A3_4") (pintype "power_in"))
      (node (ref "R14") (pin "1") (pinfunction "1_1") (pintype "passive"))
    )
    (net (code "15") (name "Net-(IC2-A4)") (class "Default")
      (node (ref "IC2") (pin "5") (pinfunction "A4_5") (pintype "power_in"))
      (node (ref "R15") (pin "1") (pinfunction "1_1") (pintype "passive"))
    )
    (net (code "16") (name "Net-(IC2-A5)") (class "Default")
      (node (ref "IC2") (pin "24") (pinfunction "A5_24") (pintype "power_in"))
      (node (ref "R16") (pin "1") (pinfunction "1_1") (pintype "passive"))
    )
    (net (code "17") (name "Net-(IC2-~{OE})") (class "Default")
      (node (ref "IC2") (pin "23") (pinfunction "~{OE}_23") (pintype "power_in"))
      (node (ref "R1") (pin "1") (pinfunction "1_1") (pintype "passive"))
    )
    (net (code "18") (name "Net-(J2-1)") (class "Default")
      (node (ref "J2") (pin "P$1") (pinfunction "1_P$1") (pintype "passive"))
      (node (ref "RELAY10") (pin "3") (pinfunction "3_3") (pintype "bidirectional"))
    )
    (net (code "19") (name "Net-(J2-2)") (class "Default")
      (node (ref "J2") (pin "P$2") (pinfunction "2_P$2") (pintype "passive"))
      (node (ref "RELAY8") (pin "3") (pinfunction "3_3") (pintype "bidirectional"))
    )
    (net (code "20") (name "Net-(J2-3)") (class "Default")
      (node (ref "J2") (pin "P$3") (pinfunction "3_P$3") (pintype "passive"))
      (node (ref "RELAY7") (pin "3") (pinfunction "3_3") (pintype "bidirectional"))
    )
    (net (code "21") (name "Net-(J2-4)") (class "Default")
      (node (ref "J2") (pin "P$4") (pinfunction "4_P$4") (pintype "passive"))
      (node (ref "RELAY6") (pin "3") (pinfunction "3_3") (pintype "bidirectional"))
    )
    (net (code "22") (name "Net-(J2-5)") (class "Default")
      (node (ref "J2") (pin "P$5") (pinfunction "5_P$5") (pintype "passive"))
      (node (ref "RELAY5") (pin "3") (pinfunction "3_3") (pintype "bidirectional"))
    )
    (net (code "23") (name "Net-(J2-6)") (class "Default")
      (node (ref "J2") (pin "P$6") (pinfunction "6_P$6") (pintype "passive"))
      (node (ref "RELAY1") (pin "3") (pinfunction "3_3") (pintype "bidirectional"))
    )
    (net (code "24") (name "Net-(J2-7)") (class "Default")
      (node (ref "J2") (pin "P$7") (pinfunction "7_P$7") (pintype "passive"))
      (node (ref "RELAY2") (pin "3") (pinfunction "3_3") (pintype "bidirectional"))
    )
    (net (code "25") (name "Net-(J2-8)") (class "Default")
      (node (ref "J2") (pin "P$8") (pinfunction "8_P$8") (pintype "passive"))
      (node (ref "RELAY3") (pin "3") (pinfunction "3_3") (pintype "bidirectional"))
    )
    (net (code "26") (name "Net-(J2-9)") (class "Default")
      (node (ref "J2") (pin "P$9") (pinfunction "9_P$9") (pintype "passive"))
      (node (ref "RELAY4") (pin "3") (pinfunction "3_3") (pintype "bidirectional"))
    )
    (net (code "27") (name "Net-(J2-10)") (class "Default")
      (node (ref "J2") (pin "P$10") (pinfunction "10_P$10") (pintype "passive"))
      (node (ref "RELAY11") (pin "3") (pinfunction "3_3") (pintype "bidirectional"))
    )
    (net (code "28") (name "Net-(J2-11)") (class "Default")
      (node (ref "J2") (pin "P$11") (pinfunction "11_P$11") (pintype "passive"))
      (node (ref "RELAY12") (pin "3") (pinfunction "3_3") (pintype "bidirectional"))
    )
    (net (code "29") (name "Net-(J2-12)") (class "Default")
      (node (ref "J2") (pin "P$12") (pinfunction "12_P$12") (pintype "passive"))
      (node (ref "RELAY13") (pin "3") (pinfunction "3_3") (pintype "bidirectional"))
    )
    (net (code "30") (name "Net-(J2-13)") (class "Default")
      (node (ref "J2") (pin "P$13") (pinfunction "13_P$13") (pintype "passive"))
      (node (ref "RELAY14") (pin "3") (pinfunction "3_3") (pintype "bidirectional"))
    )
    (net (code "31") (name "Net-(J2-14)") (class "Default")
      (node (ref "J2") (pin "P$14") (pinfunction "14_P$14") (pintype "passive"))
      (node (ref "RELAY15") (pin "3") (pinfunction "3_3") (pintype "bidirectional"))
    )
    (net (code "32") (name "Net-(J2-15)") (class "Default")
      (node (ref "J2") (pin "P$15") (pinfunction "15_P$15") (pintype "passive"))
      (node (ref "RELAY16") (pin "3") (pinfunction "3_3") (pintype "bidirectional"))
    )
    (net (code "33") (name "Net-(J2-16)") (class "Default")
      (node (ref "J2") (pin "P$16") (pinfunction "16_P$16") (pintype "passive"))
      (node (ref "RELAY17") (pin "3") (pinfunction "3_3") (pintype "bidirectional"))
    )
    (net (code "34") (name "Net-(J2-17)") (class "Default")
      (node (ref "J2") (pin "P$17") (pinfunction "17_P$17") (pintype "passive"))
      (node (ref "RELAY18") (pin "3") (pinfunction "3_3") (pintype "bidirectional"))
    )
    (net (code "35") (name "Net-(J2-18)") (class "Default")
      (node (ref "J2") (pin "P$18") (pinfunction "18_P$18") (pintype "passive"))
      (node (ref "RELAY19") (pin "3") (pinfunction "3_3") (pintype "bidirectional"))
    )
    (net (code "36") (name "Net-(J2-19)") (class "Default")
      (node (ref "J2") (pin "P$19") (pinfunction "19_P$19") (pintype "passive"))
      (node (ref "RELAY20") (pin "3") (pinfunction "3_3") (pintype "bidirectional"))
    )
    (net (code "37") (name "Net-(J2-20)") (class "Default")
      (node (ref "J2") (pin "P$20") (pinfunction "20_P$20") (pintype "passive"))
      (node (ref "RELAY21") (pin "3") (pinfunction "3_3") (pintype "bidirectional"))
    )
    (net (code "38") (name "Net-(J2-21)") (class "Default")
      (node (ref "J2") (pin "P$21") (pinfunction "21_P$21") (pintype "passive"))
      (node (ref "RELAY22") (pin "3") (pinfunction "3_3") (pintype "bidirectional"))
    )
    (net (code "39") (name "Net-(J2-22)") (class "Default")
      (node (ref "J2") (pin "P$22") (pinfunction "22_P$22") (pintype "passive"))
      (node (ref "RELAY23") (pin "3") (pinfunction "3_3") (pintype "bidirectional"))
    )
    (net (code "40") (name "Net-(J2-23)") (class "Default")
      (node (ref "J2") (pin "P$23") (pinfunction "23_P$23") (pintype "passive"))
      (node (ref "RELAY24") (pin "3") (pinfunction "3_3") (pintype "bidirectional"))
    )
    (net (code "41") (name "Net-(J2-24)") (class "Default")
      (node (ref "J2") (pin "P$24") (pinfunction "24_P$24") (pintype "passive"))
      (node (ref "RELAY25") (pin "3") (pinfunction "3_3") (pintype "bidirectional"))
    )
    (net (code "42") (name "Net-(J2-25)") (class "Default")
      (node (ref "J2") (pin "P$25") (pinfunction "25_P$25") (pintype "passive"))
      (node (ref "RELAY26") (pin "3") (pinfunction "3_3") (pintype "bidirectional"))
    )
    (net (code "43") (name "Net-(J2-26)") (class "Default")
      (node (ref "J2") (pin "P$26") (pinfunction "26_P$26") (pintype "passive"))
      (node (ref "RELAY27") (pin "3") (pinfunction "3_3") (pintype "bidirectional"))
    )
    (net (code "44") (name "Net-(J2-27)") (class "Default")
      (node (ref "J2") (pin "P$27") (pinfunction "27_P$27") (pintype "passive"))
      (node (ref "RELAY28") (pin "3") (pinfunction "3_3") (pintype "bidirectional"))
    )
    (net (code "45") (name "Net-(J2-28)") (class "Default")
      (node (ref "J2") (pin "P$28") (pinfunction "28_P$28") (pintype "passive"))
      (node (ref "RELAY29") (pin "3") (pinfunction "3_3") (pintype "bidirectional"))
    )
    (net (code "46") (name "Net-(J2-29)") (class "Default")
      (node (ref "J2") (pin "P$29") (pinfunction "29_P$29") (pintype "passive"))
      (node (ref "RELAY30") (pin "3") (pinfunction "3_3") (pintype "bidirectional"))
    )
    (net (code "47") (name "Net-(J2-30)") (class "Default")
      (node (ref "J2") (pin "P$30") (pinfunction "30_P$30") (pintype "passive"))
      (node (ref "RELAY31") (pin "3") (pinfunction "3_3") (pintype "bidirectional"))
    )
    (net (code "48") (name "Net-(J2-31)") (class "Default")
      (node (ref "J2") (pin "P$31") (pinfunction "31_P$31") (pintype "passive"))
      (node (ref "RELAY32") (pin "3") (pinfunction "3_3") (pintype "bidirectional"))
    )
    (net (code "49") (name "Net-(J2-32)") (class "Default")
      (node (ref "J2") (pin "P$32") (pinfunction "32_P$32") (pintype "passive"))
      (node (ref "RELAY33") (pin "3") (pinfunction "3_3") (pintype "bidirectional"))
    )
    (net (code "50") (name "Net-(R9-Pad2)") (class "Default")
      (node (ref "R9") (pin "2") (pinfunction "2_2") (pintype "passive"))
      (node (ref "RELAY10") (pin "2") (pinfunction "2_2") (pintype "bidirectional"))
    )
    (net (code "51") (name "Net-(R10-Pad2)") (class "Default")
      (node (ref "R10") (pin "2") (pinfunction "2_2") (pintype "passive"))
      (node (ref "RELAY8") (pin "2") (pinfunction "2_2") (pintype "bidirectional"))
    )
    (net (code "52") (name "Net-(R19-Pad2)") (class "Default")
      (node (ref "R19") (pin "2") (pinfunction "2_2") (pintype "passive"))
      (node (ref "RELAY7") (pin "2") (pinfunction "2_2") (pintype "bidirectional"))
    )
    (net (code "53") (name "Net-(R21-Pad2)") (class "Default")
      (node (ref "R21") (pin "2") (pinfunction "2_2") (pintype "passive"))
      (node (ref "RELAY6") (pin "2") (pinfunction "2_2") (pintype "bidirectional"))
    )
    (net (code "54") (name "Net-(R22-Pad2)") (class "Default")
      (node (ref "R22") (pin "2") (pinfunction "2_2") (pintype "passive"))
      (node (ref "RELAY5") (pin "2") (pinfunction "2_2") (pintype "bidirectional"))
    )
    (net (code "55") (name "Net-(R23-Pad2)") (class "Default")
      (node (ref "R23") (pin "2") (pinfunction "2_2") (pintype "passive"))
      (node (ref "RELAY1") (pin "2") (pinfunction "2_2") (pintype "bidirectional"))
    )
    (net (code "56") (name "Net-(R24-Pad2)") (class "Default")
      (node (ref "R24") (pin "2") (pinfunction "2_2") (pintype "passive"))
      (node (ref "RELAY2") (pin "2") (pinfunction "2_2") (pintype "bidirectional"))
    )
    (net (code "57") (name "Net-(R25-Pad2)") (class "Default")
      (node (ref "R25") (pin "2") (pinfunction "2_2") (pintype "passive"))
      (node (ref "RELAY3") (pin "2") (pinfunction "2_2") (pintype "bidirectional"))
    )
    (net (code "58") (name "Net-(R26-Pad2)") (class "Default")
      (node (ref "R26") (pin "2") (pinfunction "2_2") (pintype "passive"))
      (node (ref "RELAY4") (pin "2") (pinfunction "2_2") (pintype "bidirectional"))
    )
    (net (code "59") (name "Net-(R27-Pad2)") (class "Default")
      (node (ref "R27") (pin "2") (pinfunction "2_2") (pintype "passive"))
      (node (ref "RELAY11") (pin "2") (pinfunction "2_2") (pintype "bidirectional"))
    )
    (net (code "60") (name "Net-(R28-Pad2)") (class "Default")
      (node (ref "R28") (pin "2") (pinfunction "2_2") (pintype "passive"))
      (node (ref "RELAY12") (pin "2") (pinfunction "2_2") (pintype "bidirectional"))
    )
    (net (code "61") (name "Net-(R29-Pad2)") (class "Default")
      (node (ref "R29") (pin "2") (pinfunction "2_2") (pintype "passive"))
      (node (ref "RELAY13") (pin "2") (pinfunction "2_2") (pintype "bidirectional"))
    )
    (net (code "62") (name "Net-(R30-Pad2)") (class "Default")
      (node (ref "R30") (pin "2") (pinfunction "2_2") (pintype "passive"))
      (node (ref "RELAY14") (pin "2") (pinfunction "2_2") (pintype "bidirectional"))
    )
    (net (code "63") (name "Net-(R31-Pad2)") (class "Default")
      (node (ref "R31") (pin "2") (pinfunction "2_2") (pintype "passive"))
      (node (ref "RELAY15") (pin "2") (pinfunction "2_2") (pintype "bidirectional"))
    )
    (net (code "64") (name "Net-(R32-Pad2)") (class "Default")
      (node (ref "R32") (pin "2") (pinfunction "2_2") (pintype "passive"))
      (node (ref "RELAY16") (pin "2") (pinfunction "2_2") (pintype "bidirectional"))
    )
    (net (code "65") (name "Net-(R33-Pad2)") (class "Default")
      (node (ref "R33") (pin "2") (pinfunction "2_2") (pintype "passive"))
      (node (ref "RELAY17") (pin "2") (pinfunction "2_2") (pintype "bidirectional"))
    )
    (net (code "66") (name "Net-(R34-Pad2)") (class "Default")
      (node (ref "R34") (pin "2") (pinfunction "2_2") (pintype "passive"))
      (node (ref "RELAY18") (pin "2") (pinfunction "2_2") (pintype "bidirectional"))
    )
    (net (code "67") (name "Net-(R35-Pad2)") (class "Default")
      (node (ref "R35") (pin "2") (pinfunction "2_2") (pintype "passive"))
      (node (ref "RELAY19") (pin "2") (pinfunction "2_2") (pintype "bidirectional"))
    )
    (net (code "68") (name "Net-(R36-Pad2)") (class "Default")
      (node (ref "R36") (pin "2") (pinfunction "2_2") (pintype "passive"))
      (node (ref "RELAY20") (pin "2") (pinfunction "2_2") (pintype "bidirectional"))
    )
    (net (code "69") (name "Net-(R37-Pad2)") (class "Default")
      (node (ref "R37") (pin "2") (pinfunction "2_2") (pintype "passive"))
      (node (ref "RELAY21") (pin "2") (pinfunction "2_2") (pintype "bidirectional"))
    )
    (net (code "70") (name "Net-(R38-Pad2)") (class "Default")
      (node (ref "R38") (pin "2") (pinfunction "2_2") (pintype "passive"))
      (node (ref "RELAY22") (pin "2") (pinfunction "2_2") (pintype "bidirectional"))
    )
    (net (code "71") (name "Net-(R39-Pad2)") (class "Default")
      (node (ref "R39") (pin "2") (pinfunction "2_2") (pintype "passive"))
      (node (ref "RELAY23") (pin "2") (pinfunction "2_2") (pintype "bidirectional"))
    )
    (net (code "72") (name "Net-(R40-Pad2)") (class "Default")
      (node (ref "R40") (pin "2") (pinfunction "2_2") (pintype "passive"))
      (node (ref "RELAY24") (pin "2") (pinfunction "2_2") (pintype "bidirectional"))
    )
    (net (code "73") (name "Net-(R41-Pad2)") (class "Default")
      (node (ref "R41") (pin "2") (pinfunction "2_2") (pintype "passive"))
      (node (ref "RELAY25") (pin "2") (pinfunction "2_2") (pintype "bidirectional"))
    )
    (net (code "74") (name "Net-(R42-Pad2)") (class "Default")
      (node (ref "R42") (pin "2") (pinfunction "2_2") (pintype "passive"))
      (node (ref "RELAY26") (pin "2") (pinfunction "2_2") (pintype "bidirectional"))
    )
    (net (code "75") (name "Net-(R43-Pad2)") (class "Default")
      (node (ref "R43") (pin "2") (pinfunction "2_2") (pintype "passive"))
      (node (ref "RELAY27") (pin "2") (pinfunction "2_2") (pintype "bidirectional"))
    )
    (net (code "76") (name "Net-(R44-Pad2)") (class "Default")
      (node (ref "R44") (pin "2") (pinfunction "2_2") (pintype "passive"))
      (node (ref "RELAY28") (pin "2") (pinfunction "2_2") (pintype "bidirectional"))
    )
    (net (code "77") (name "Net-(R45-Pad2)") (class "Default")
      (node (ref "R45") (pin "2") (pinfunction "2_2") (pintype "passive"))
      (node (ref "RELAY29") (pin "2") (pinfunction "2_2") (pintype "bidirectional"))
    )
    (net (code "78") (name "Net-(R46-Pad2)") (class "Default")
      (node (ref "R46") (pin "2") (pinfunction "2_2") (pintype "passive"))
      (node (ref "RELAY30") (pin "2") (pinfunction "2_2") (pintype "bidirectional"))
    )
    (net (code "79") (name "Net-(R47-Pad2)") (class "Default")
      (node (ref "R47") (pin "2") (pinfunction "2_2") (pintype "passive"))
      (node (ref "RELAY31") (pin "2") (pinfunction "2_2") (pintype "bidirectional"))
    )
    (net (code "80") (name "Net-(R48-Pad2)") (class "Default")
      (node (ref "R48") (pin "2") (pinfunction "2_2") (pintype "passive"))
      (node (ref "RELAY32") (pin "2") (pinfunction "2_2") (pintype "bidirectional"))
    )
    (net (code "81") (name "Net-(R49-Pad2)") (class "Default")
      (node (ref "R49") (pin "2") (pinfunction "2_2") (pintype "passive"))
      (node (ref "RELAY33") (pin "2") (pinfunction "2_2") (pintype "bidirectional"))
    )
    (net (code "82") (name "SW") (class "Default")
      (node (ref "IC1") (pin "18") (pinfunction "PWM11_18") (pintype "output"))
      (node (ref "J5") (pin "12") (pinfunction "12_12") (pintype "passive"))
      (node (ref "RELAY13") (pin "1") (pinfunction "1_1") (pintype "bidirectional"))
    )
    (net (code "83") (name "SW1") (class "Default")
      (node (ref "IC1") (pin "6") (pinfunction "PWM0_6") (pintype "output"))
      (node (ref "J5") (pin "1") (pinfunction "1_1") (pintype "passive"))
      (node (ref "RELAY10") (pin "1") (pinfunction "1_1") (pintype "bidirectional"))
    )
    (net (code "84") (name "SW2") (class "Default")
      (node (ref "IC1") (pin "7") (pinfunction "PWM1_7") (pintype "output"))
      (node (ref "J5") (pin "2") (pinfunction "2_2") (pintype "passive"))
      (node (ref "RELAY8") (pin "1") (pinfunction "1_1") (pintype "bidirectional"))
    )
    (net (code "85") (name "SW3") (class "Default")
      (node (ref "IC1") (pin "8") (pinfunction "PWM2_8") (pintype "output"))
      (node (ref "J5") (pin "3") (pinfunction "3_3") (pintype "passive"))
      (node (ref "RELAY7") (pin "1") (pinfunction "1_1") (pintype "bidirectional"))
    )
    (net (code "86") (name "SW4") (class "Default")
      (node (ref "IC1") (pin "9") (pinfunction "PWM3_9") (pintype "output"))
      (node (ref "J5") (pin "4") (pinfunction "4_4") (pintype "passive"))
      (node (ref "RELAY6") (pin "1") (pinfunction "1_1") (pintype "bidirectional"))
    )
    (net (code "87") (name "SW5") (class "Default")
      (node (ref "IC1") (pin "10") (pinfunction "PWM4_10") (pintype "output"))
      (node (ref "J5") (pin "5") (pinfunction "5_5") (pintype "passive"))
      (node (ref "RELAY5") (pin "1") (pinfunction "1_1") (pintype "bidirectional"))
    )
    (net (code "88") (name "SW6") (class "Default")
      (node (ref "IC1") (pin "11") (pinfunction "PWM5_11") (pintype "output"))
      (node (ref "J5") (pin "6") (pinfunction "6_6") (pintype "passive"))
      (node (ref "RELAY1") (pin "1") (pinfunction "1_1") (pintype "bidirectional"))
    )
    (net (code "89") (name "SW7") (class "Default")
      (node (ref "IC1") (pin "12") (pinfunction "PWM6_12") (pintype "output"))
      (node (ref "J5") (pin "7") (pinfunction "7_7") (pintype "passive"))
      (node (ref "RELAY2") (pin "1") (pinfunction "1_1") (pintype "bidirectional"))
    )
    (net (code "90") (name "SW8") (class "Default")
      (node (ref "IC1") (pin "13") (pinfunction "PWM7_13") (pintype "output"))
      (node (ref "J5") (pin "8") (pinfunction "8_8") (pintype "passive"))
      (node (ref "RELAY3") (pin "1") (pinfunction "1_1") (pintype "bidirectional"))
    )
    (net (code "91") (name "SW9") (class "Default")
      (node (ref "IC1") (pin "15") (pinfunction "PWM8_15") (pintype "output"))
      (node (ref "J5") (pin "9") (pinfunction "9_9") (pintype "passive"))
      (node (ref "RELAY4") (pin "1") (pinfunction "1_1") (pintype "bidirectional"))
    )
    (net (code "92") (name "SW10") (class "Default")
      (node (ref "IC1") (pin "16") (pinfunction "PWM9_16") (pintype "output"))
      (node (ref "J5") (pin "10") (pinfunction "10_10") (pintype "passive"))
      (node (ref "RELAY11") (pin "1") (pinfunction "1_1") (pintype "bidirectional"))
    )
    (net (code "93") (name "SW11") (class "Default")
      (node (ref "IC1") (pin "17") (pinfunction "PWM10_17") (pintype "output"))
      (node (ref "J5") (pin "11") (pinfunction "11_11") (pintype "passive"))
      (node (ref "RELAY12") (pin "1") (pinfunction "1_1") (pintype "bidirectional"))
    )
    (net (code "94") (name "SW13") (class "Default")
      (node (ref "IC1") (pin "19") (pinfunction "PWM12_19") (pintype "output"))
      (node (ref "J5") (pin "13") (pinfunction "13_13") (pintype "passive"))
      (node (ref "RELAY14") (pin "1") (pinfunction "1_1") (pintype "bidirectional"))
    )
    (net (code "95") (name "SW14") (class "Default")
      (node (ref "IC1") (pin "20") (pinfunction "PWM13_20") (pintype "output"))
      (node (ref "J5") (pin "14") (pinfunction "14_14") (pintype "passive"))
      (node (ref "RELAY15") (pin "1") (pinfunction "1_1") (pintype "bidirectional"))
    )
    (net (code "96") (name "SW15") (class "Default")
      (node (ref "IC1") (pin "21") (pinfunction "PWM14_21") (pintype "output"))
      (node (ref "J5") (pin "15") (pinfunction "15_15") (pintype "passive"))
      (node (ref "RELAY16") (pin "1") (pinfunction "1_1") (pintype "bidirectional"))
    )
    (net (code "97") (name "SW16") (class "Default")
      (node (ref "IC1") (pin "22") (pinfunction "PWM15_22") (pintype "output"))
      (node (ref "J5") (pin "16") (pinfunction "16_16") (pintype "passive"))
      (node (ref "RELAY17") (pin "1") (pinfunction "1_1") (pintype "bidirectional"))
    )
    (net (code "98") (name "SW17") (class "Default")
      (node (ref "IC2") (pin "6") (pinfunction "PWM0_6") (pintype "output"))
      (node (ref "J5") (pin "17") (pinfunction "17_17") (pintype "passive"))
      (node (ref "RELAY18") (pin "1") (pinfunction "1_1") (pintype "bidirectional"))
    )
    (net (code "99") (name "SW18") (class "Default")
      (node (ref "IC2") (pin "7") (pinfunction "PWM1_7") (pintype "output"))
      (node (ref "J5") (pin "18") (pinfunction "18_18") (pintype "passive"))
      (node (ref "RELAY19") (pin "1") (pinfunction "1_1") (pintype "bidirectional"))
    )
    (net (code "100") (name "SW19") (class "Default")
      (node (ref "IC2") (pin "8") (pinfunction "PWM2_8") (pintype "output"))
      (node (ref "J5") (pin "19") (pinfunction "19_19") (pintype "passive"))
      (node (ref "RELAY20") (pin "1") (pinfunction "1_1") (pintype "bidirectional"))
    )
    (net (code "101") (name "SW20") (class "Default")
      (node (ref "IC2") (pin "9") (pinfunction "PWM3_9") (pintype "output"))
      (node (ref "J5") (pin "20") (pinfunction "20_20") (pintype "passive"))
      (node (ref "RELAY21") (pin "1") (pinfunction "1_1") (pintype "bidirectional"))
    )
    (net (code "102") (name "SW21") (class "Default")
      (node (ref "IC2") (pin "10") (pinfunction "PWM4_10") (pintype "output"))
      (node (ref "J5") (pin "21") (pinfunction "21_21") (pintype "passive"))
      (node (ref "RELAY22") (pin "1") (pinfunction "1_1") (pintype "bidirectional"))
    )
    (net (code "103") (name "SW22") (class "Default")
      (node (ref "IC2") (pin "11") (pinfunction "PWM5_11") (pintype "output"))
      (node (ref "J5") (pin "22") (pinfunction "22_22") (pintype "passive"))
      (node (ref "RELAY23") (pin "1") (pinfunction "1_1") (pintype "bidirectional"))
    )
    (net (code "104") (name "SW23") (class "Default")
      (node (ref "IC2") (pin "12") (pinfunction "PWM6_12") (pintype "output"))
      (node (ref "J5") (pin "23") (pinfunction "23_23") (pintype "passive"))
      (node (ref "RELAY24") (pin "1") (pinfunction "1_1") (pintype "bidirectional"))
    )
    (net (code "105") (name "SW24") (class "Default")
      (node (ref "IC2") (pin "13") (pinfunction "PWM7_13") (pintype "output"))
      (node (ref "J5") (pin "24") (pinfunction "24_24") (pintype "passive"))
      (node (ref "RELAY25") (pin "1") (pinfunction "1_1") (pintype "bidirectional"))
    )
    (net (code "106") (name "SW25") (class "Default")
      (node (ref "IC2") (pin "15") (pinfunction "PWM8_15") (pintype "output"))
      (node (ref "J5") (pin "25") (pinfunction "25_25") (pintype "passive"))
      (node (ref "RELAY26") (pin "1") (pinfunction "1_1") (pintype "bidirectional"))
    )
    (net (code "107") (name "SW26") (class "Default")
      (node (ref "IC2") (pin "16") (pinfunction "PWM9_16") (pintype "output"))
      (node (ref "J5") (pin "26") (pinfunction "26_26") (pintype "passive"))
      (node (ref "RELAY27") (pin "1") (pinfunction "1_1") (pintype "bidirectional"))
    )
    (net (code "108") (name "SW27") (class "Default")
      (node (ref "IC2") (pin "17") (pinfunction "PWM10_17") (pintype "output"))
      (node (ref "J5") (pin "27") (pinfunction "27_27") (pintype "passive"))
      (node (ref "RELAY28") (pin "1") (pinfunction "1_1") (pintype "bidirectional"))
    )
    (net (code "109") (name "SW28") (class "Default")
      (node (ref "IC2") (pin "18") (pinfunction "PWM11_18") (pintype "output"))
      (node (ref "J5") (pin "28") (pinfunction "28_28") (pintype "passive"))
      (node (ref "RELAY29") (pin "1") (pinfunction "1_1") (pintype "bidirectional"))
    )
    (net (code "110") (name "SW29") (class "Default")
      (node (ref "IC2") (pin "19") (pinfunction "PWM12_19") (pintype "output"))
      (node (ref "J5") (pin "29") (pinfunction "29_29") (pintype "passive"))
      (node (ref "RELAY30") (pin "1") (pinfunction "1_1") (pintype "bidirectional"))
    )
    (net (code "111") (name "SW30") (class "Default")
      (node (ref "IC2") (pin "20") (pinfunction "PWM13_20") (pintype "output"))
      (node (ref "J5") (pin "30") (pinfunction "30_30") (pintype "passive"))
      (node (ref "RELAY31") (pin "1") (pinfunction "1_1") (pintype "bidirectional"))
    )
    (net (code "112") (name "SW31") (class "Default")
      (node (ref "IC2") (pin "21") (pinfunction "PWM14_21") (pintype "output"))
      (node (ref "J5") (pin "31") (pinfunction "31_31") (pintype "passive"))
      (node (ref "RELAY32") (pin "1") (pinfunction "1_1") (pintype "bidirectional"))
    )
    (net (code "113") (name "SW32") (class "Default")
      (node (ref "IC2") (pin "22") (pinfunction "PWM15_22") (pintype "output"))
      (node (ref "J5") (pin "32") (pinfunction "32_32") (pintype "passive"))
      (node (ref "RELAY33") (pin "1") (pinfunction "1_1") (pintype "bidirectional"))
    )
    (net (code "114") (name "VCC") (class "Default")
      (node (ref "C1") (pin "1") (pinfunction "1_1") (pintype "passive"))
      (node (ref "C2") (pin "1") (pinfunction "1_1") (pintype "passive"))
      (node (ref "IC1") (pin "1") (pinfunction "A0_1") (pintype "power_in"))
      (node (ref "IC1") (pin "28") (pinfunction "VCC_28") (pintype "power_in"))
      (node (ref "IC2") (pin "2") (pinfunction "A1_2") (pintype "power_in"))
      (node (ref "IC2") (pin "28") (pinfunction "VCC_28") (pintype "power_in"))
      (node (ref "J4") (pin "1") (pinfunction "1_1") (pintype "passive"))
      (node (ref "R17") (pin "1") (pinfunction "1_1") (pintype "passive"))
      (node (ref "R18") (pin "2") (pinfunction "2_2") (pintype "passive"))
      (node (ref "R2") (pin "1") (pinfunction "1_1") (pintype "passive"))
      (node (ref "R4") (pin "1") (pinfunction "1_1") (pintype "passive"))
    )
  )
)
